# solo.net
KiCad netlist of a schematic drawn in EAGLE
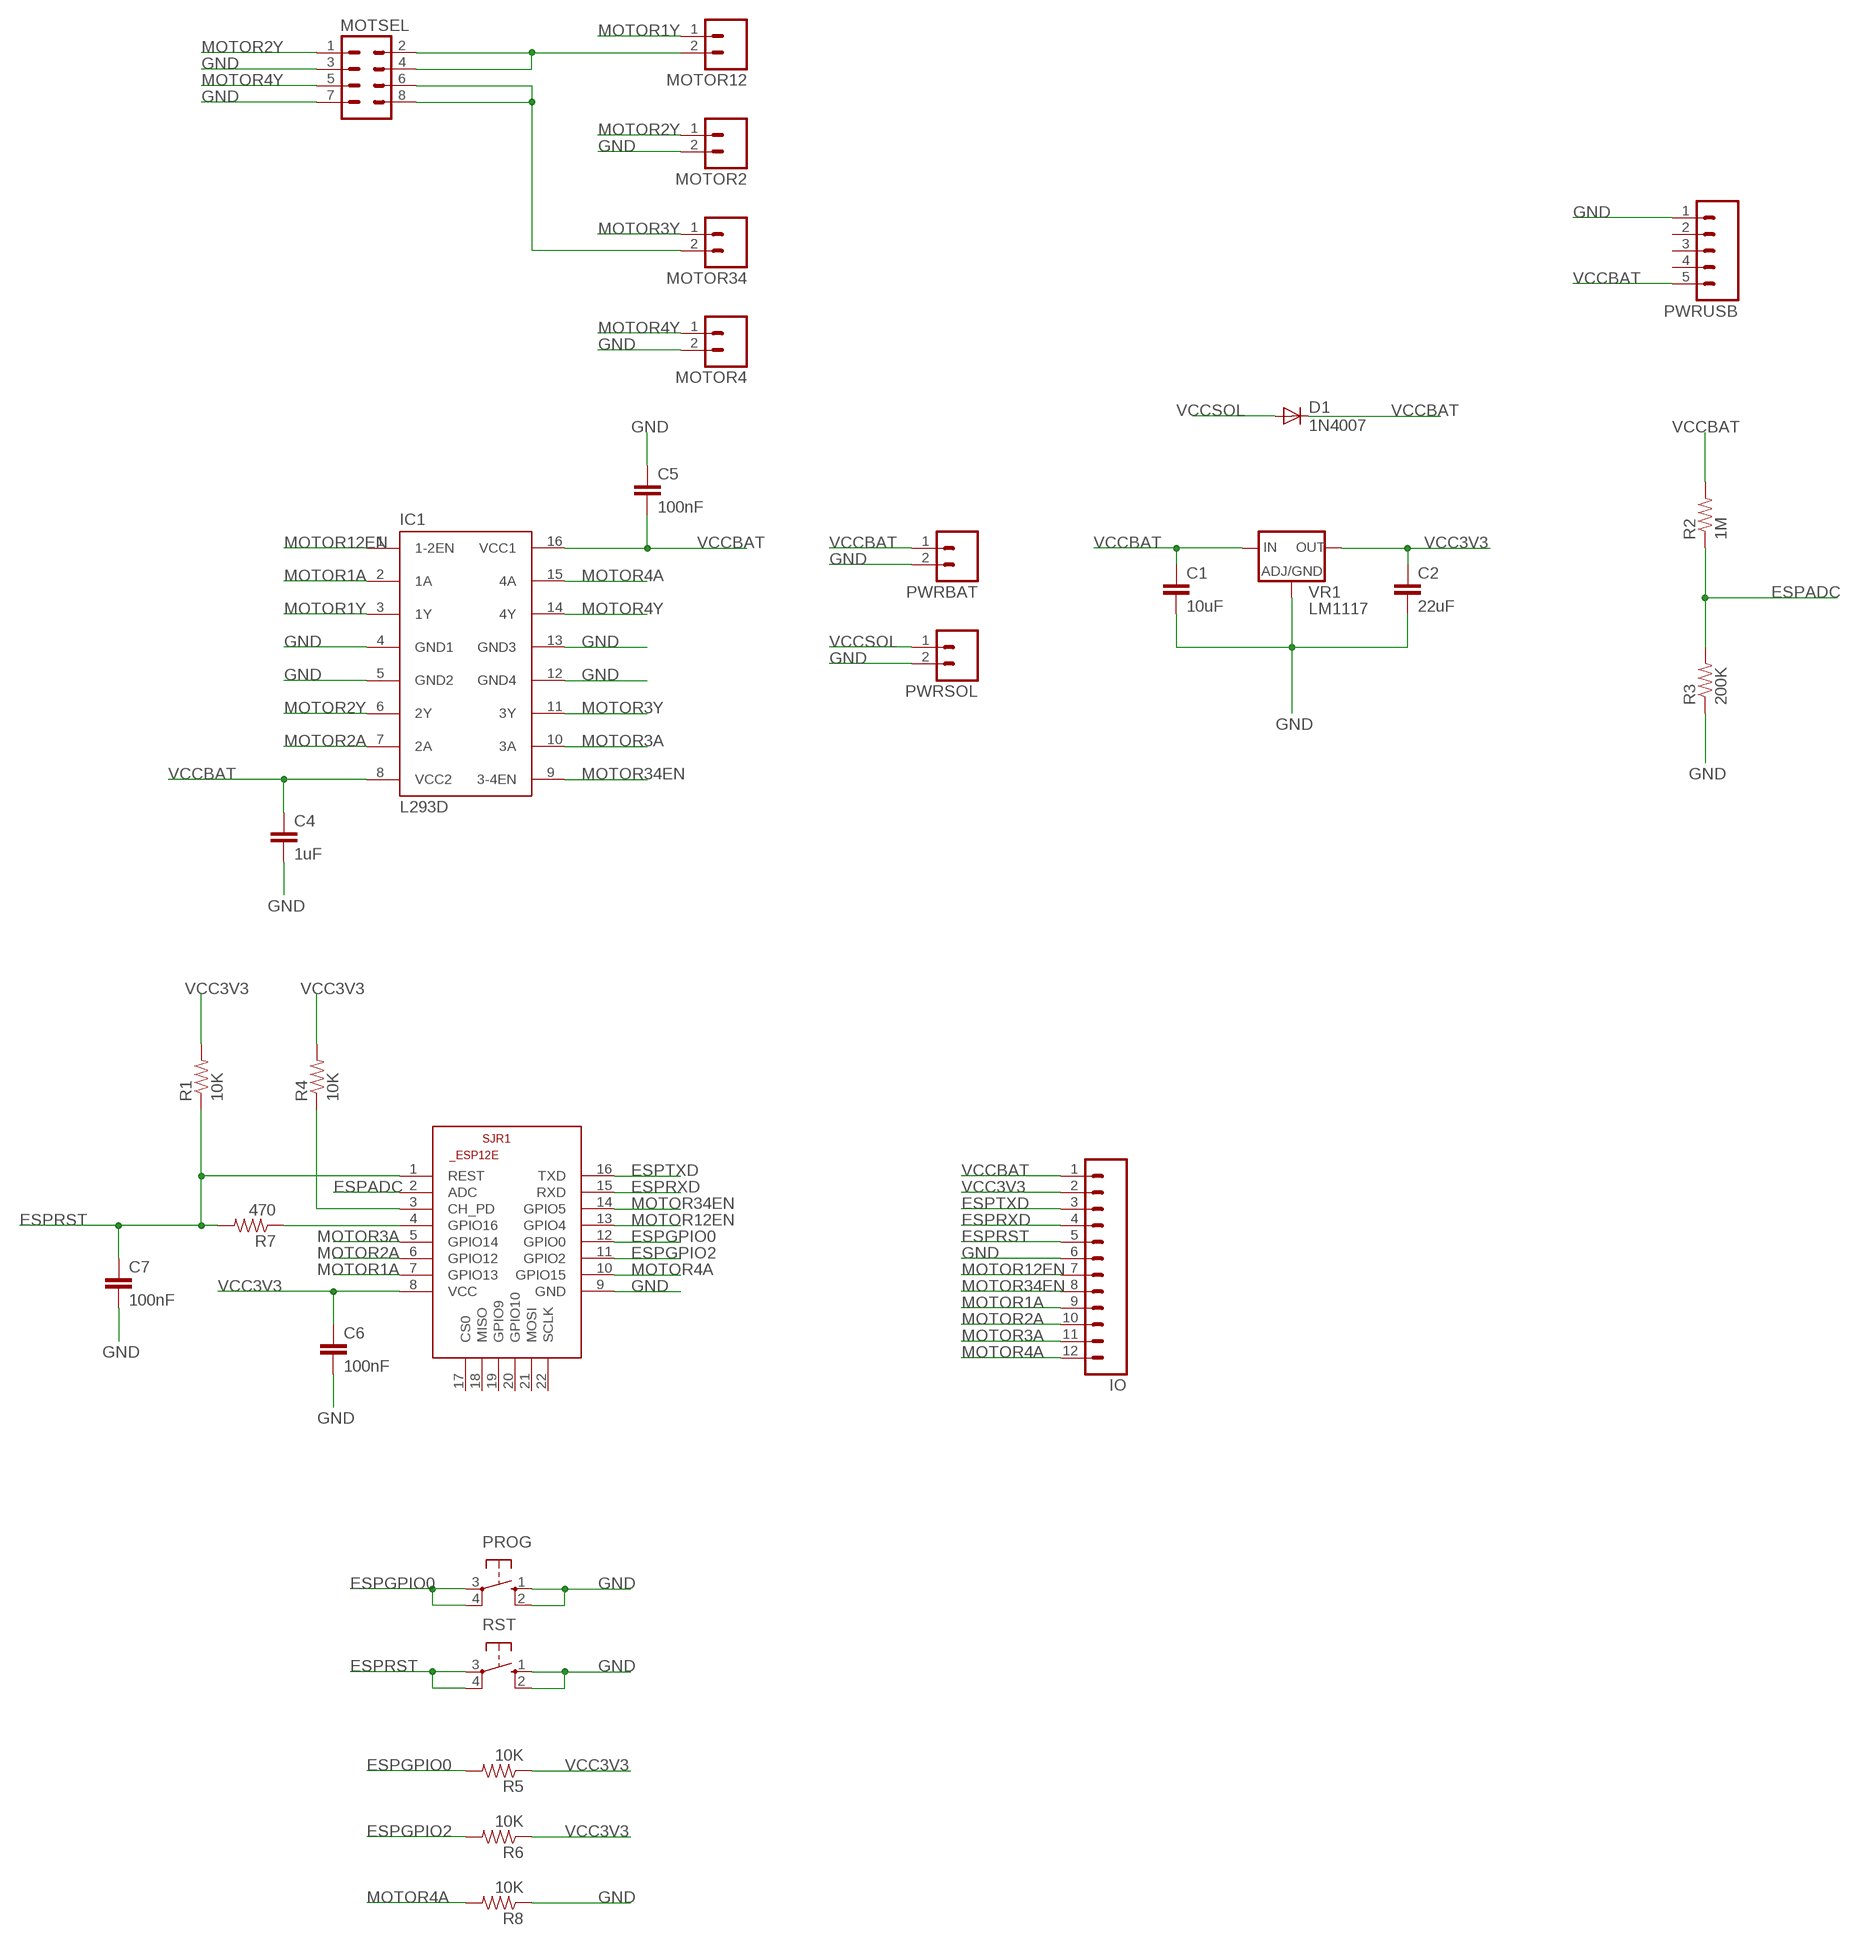
[diagram p0: schematic, sheet 1]

(export (version "E")
  (design (tool "Eeschema 10.0.6"))
  (components
    (comp (ref "C1")
      (value "10uF")
      (footprint "eagle-import:1206")
      (libsource (lib "eagle-import") (part "CAP1206"))
    )
    (comp (ref "C2")
      (value "22uF")
      (footprint "eagle-import:1206")
      (libsource (lib "eagle-import") (part "CAP1206"))
    )
    (comp (ref "C4")
      (value "1uF")
      (footprint "eagle-import:1206")
      (libsource (lib "eagle-import") (part "CAP1206"))
    )
    (comp (ref "C5")
      (value "100nF")
      (footprint "eagle-import:1206")
      (libsource (lib "eagle-import") (part "CAP1206"))
    )
    (comp (ref "C6")
      (value "100nF")
      (footprint "eagle-import:1206")
      (libsource (lib "eagle-import") (part "CAP1206"))
    )
    (comp (ref "C7")
      (value "100nF")
      (footprint "eagle-import:1206")
      (libsource (lib "eagle-import") (part "CAP1206"))
    )
    (comp (ref "D1")
      (value "1N4007")
      (footprint "eagle-import:DO41-10")
      (libsource (lib "eagle-import") (part "1N4004"))
    )
    (comp (ref "IC1")
      (value "L293D")
      (footprint "eagle-import:DIL16")
      (libsource (lib "eagle-import") (part "L293D"))
    )
    (comp (ref "IO")
      (value "M12PTH")
      (footprint "eagle-import:1X12")
      (libsource (lib "eagle-import") (part "M12PTH"))
    )
    (comp (ref "MOTOR2")
      (value "M023.5MM")
      (footprint "eagle-import:SCREWTERMINAL-3.5MM-2")
      (libsource (lib "eagle-import") (part "M023.5MM"))
    )
    (comp (ref "MOTOR4")
      (value "M023.5MM")
      (footprint "eagle-import:SCREWTERMINAL-3.5MM-2")
      (libsource (lib "eagle-import") (part "M023.5MM"))
    )
    (comp (ref "MOTOR12")
      (value "M023.5MM")
      (footprint "eagle-import:SCREWTERMINAL-3.5MM-2")
      (libsource (lib "eagle-import") (part "M023.5MM"))
    )
    (comp (ref "MOTOR34")
      (value "M023.5MM")
      (footprint "eagle-import:SCREWTERMINAL-3.5MM-2")
      (libsource (lib "eagle-import") (part "M023.5MM"))
    )
    (comp (ref "MOTSEL")
      (value "M04X2")
      (footprint "eagle-import:2X4")
      (libsource (lib "eagle-import") (part "M04X2"))
    )
    (comp (ref "PROG")
      (value "10-XX")
      (footprint "eagle-import:B3F-10XX")
      (fields (field (name "MPN") "B3F-1000"))
      (libsource (lib "eagle-import") (part "10-XX"))
    )
    (comp (ref "PWRBAT")
      (value "M023.5MM")
      (footprint "eagle-import:SCREWTERMINAL-3.5MM-2")
      (libsource (lib "eagle-import") (part "M023.5MM"))
    )
    (comp (ref "PWRSOL")
      (value "M023.5MM")
      (footprint "eagle-import:SCREWTERMINAL-3.5MM-2")
      (libsource (lib "eagle-import") (part "M023.5MM"))
    )
    (comp (ref "PWRUSB")
      (value "M05PTH")
      (footprint "eagle-import:1X05")
      (libsource (lib "eagle-import") (part "M05PTH"))
    )
    (comp (ref "R1")
      (value "10K")
      (footprint "eagle-import:1206")
      (libsource (lib "eagle-import") (part "RESISTOR1206"))
    )
    (comp (ref "R2")
      (value "1M")
      (footprint "eagle-import:1206")
      (libsource (lib "eagle-import") (part "RESISTOR1206"))
    )
    (comp (ref "R3")
      (value "200K")
      (footprint "eagle-import:1206")
      (libsource (lib "eagle-import") (part "RESISTOR1206"))
    )
    (comp (ref "R4")
      (value "10K")
      (footprint "eagle-import:1206")
      (libsource (lib "eagle-import") (part "RESISTOR1206"))
    )
    (comp (ref "R5")
      (value "10K")
      (footprint "eagle-import:1206")
      (libsource (lib "eagle-import") (part "RESISTOR1206"))
    )
    (comp (ref "R6")
      (value "10K")
      (footprint "eagle-import:1206")
      (libsource (lib "eagle-import") (part "RESISTOR1206"))
    )
    (comp (ref "R7")
      (value "470")
      (footprint "eagle-import:1206")
      (libsource (lib "eagle-import") (part "RESISTOR1206"))
    )
    (comp (ref "R8")
      (value "10K")
      (footprint "eagle-import:1206")
      (libsource (lib "eagle-import") (part "RESISTOR1206"))
    )
    (comp (ref "RST")
      (value "10-XX")
      (footprint "eagle-import:B3F-10XX")
      (fields (field (name "MPN") "B3F-1000"))
      (libsource (lib "eagle-import") (part "10-XX"))
    )
    (comp (ref "SJR1")
      (value "ESP8266-12EESP12E")
      (footprint "eagle-import:ESP8266-ESP12E")
      (libsource (lib "eagle-import") (part "ESP8266-12EESP12E"))
    )
    (comp (ref "VR1")
      (value "LM1117")
      (footprint "eagle-import:SOT223")
      (libsource (lib "eagle-import") (part "LM1117"))
    )
  )
  (nets
    (net (code "1") (name "/ESPADC") (class "Default")
      (node (ref "R2") (pin "1") (pinfunction "1_1") (pintype "passive"))
      (node (ref "R3") (pin "2") (pinfunction "2_2") (pintype "passive"))
      (node (ref "SJR1") (pin "2") (pinfunction "ADC_2") (pintype "bidirectional"))
    )
    (net (code "2") (name "/ESPGPIO0") (class "Default")
      (node (ref "PROG") (pin "3") (pinfunction "P_3") (pintype "passive"))
      (node (ref "PROG") (pin "4") (pinfunction "P1_4") (pintype "passive"))
      (node (ref "R5") (pin "2") (pinfunction "2_2") (pintype "passive"))
      (node (ref "SJR1") (pin "12") (pinfunction "GPIO0_12") (pintype "bidirectional"))
    )
    (net (code "3") (name "/ESPGPIO2") (class "Default")
      (node (ref "R6") (pin "2") (pinfunction "2_2") (pintype "passive"))
      (node (ref "SJR1") (pin "11") (pinfunction "GPIO2_11") (pintype "bidirectional"))
    )
    (net (code "4") (name "/ESPRST") (class "Default")
      (node (ref "C7") (pin "1") (pinfunction "1_1") (pintype "passive"))
      (node (ref "IO") (pin "5") (pinfunction "5_5") (pintype "passive"))
      (node (ref "R1") (pin "1") (pinfunction "1_1") (pintype "passive"))
      (node (ref "R7") (pin "2") (pinfunction "2_2") (pintype "passive"))
      (node (ref "RST") (pin "3") (pinfunction "P_3") (pintype "passive"))
      (node (ref "RST") (pin "4") (pinfunction "P1_4") (pintype "passive"))
      (node (ref "SJR1") (pin "1") (pinfunction "REST_1") (pintype "bidirectional"))
    )
    (net (code "5") (name "/ESPRXD") (class "Default")
      (node (ref "IO") (pin "4") (pinfunction "4_4") (pintype "passive"))
      (node (ref "SJR1") (pin "15") (pinfunction "RXD_15") (pintype "bidirectional"))
    )
    (net (code "6") (name "/ESPTXD") (class "Default")
      (node (ref "IO") (pin "3") (pinfunction "3_3") (pintype "passive"))
      (node (ref "SJR1") (pin "16") (pinfunction "TXD_16") (pintype "bidirectional"))
    )
    (net (code "7") (name "/GND") (class "Default")
      (node (ref "C1") (pin "2") (pinfunction "2_2") (pintype "passive"))
      (node (ref "C2") (pin "2") (pinfunction "2_2") (pintype "passive"))
      (node (ref "C4") (pin "2") (pinfunction "2_2") (pintype "passive"))
      (node (ref "C5") (pin "1") (pinfunction "1_1") (pintype "passive"))
      (node (ref "C6") (pin "2") (pinfunction "2_2") (pintype "passive"))
      (node (ref "C7") (pin "2") (pinfunction "2_2") (pintype "passive"))
      (node (ref "IC1") (pin "12") (pinfunction "GND4_12") (pintype "power_in"))
      (node (ref "IC1") (pin "13") (pinfunction "GND3_13") (pintype "power_in"))
      (node (ref "IC1") (pin "4") (pinfunction "GND1_4") (pintype "power_in"))
      (node (ref "IC1") (pin "5") (pinfunction "GND2_5") (pintype "power_in"))
      (node (ref "IO") (pin "6") (pinfunction "6_6") (pintype "passive"))
      (node (ref "MOTOR2") (pin "2") (pinfunction "2_2") (pintype "passive"))
      (node (ref "MOTOR4") (pin "2") (pinfunction "2_2") (pintype "passive"))
      (node (ref "MOTSEL") (pin "3") (pinfunction "3_3") (pintype "passive"))
      (node (ref "MOTSEL") (pin "7") (pinfunction "7_7") (pintype "passive"))
      (node (ref "PROG") (pin "1") (pinfunction "S_1") (pintype "passive"))
      (node (ref "PROG") (pin "2") (pinfunction "S1_2") (pintype "passive"))
      (node (ref "PWRBAT") (pin "2") (pinfunction "2_2") (pintype "passive"))
      (node (ref "PWRSOL") (pin "2") (pinfunction "2_2") (pintype "passive"))
      (node (ref "PWRUSB") (pin "1") (pinfunction "1_1") (pintype "passive"))
      (node (ref "R3") (pin "1") (pinfunction "1_1") (pintype "passive"))
      (node (ref "R8") (pin "1") (pinfunction "1_1") (pintype "passive"))
      (node (ref "RST") (pin "1") (pinfunction "S_1") (pintype "passive"))
      (node (ref "RST") (pin "2") (pinfunction "S1_2") (pintype "passive"))
      (node (ref "SJR1") (pin "9") (pinfunction "GND_9") (pintype "bidirectional"))
      (node (ref "VR1") (pin "1") (pinfunction "ADJ/GND_1") (pintype "power_in"))
    )
    (net (code "8") (name "/MOTOR1A") (class "Default")
      (node (ref "IC1") (pin "2") (pinfunction "1A_2") (pintype "input"))
      (node (ref "IO") (pin "9") (pinfunction "9_9") (pintype "passive"))
      (node (ref "SJR1") (pin "7") (pinfunction "GPIO13_7") (pintype "bidirectional"))
    )
    (net (code "9") (name "/MOTOR1Y") (class "Default")
      (node (ref "IC1") (pin "3") (pinfunction "1Y_3") (pintype "output"))
      (node (ref "MOTOR12") (pin "1") (pinfunction "1_1") (pintype "passive"))
    )
    (net (code "10") (name "/MOTOR2A") (class "Default")
      (node (ref "IC1") (pin "7") (pinfunction "2A_7") (pintype "input"))
      (node (ref "IO") (pin "10") (pinfunction "10_10") (pintype "passive"))
      (node (ref "SJR1") (pin "6") (pinfunction "GPIO12_6") (pintype "bidirectional"))
    )
    (net (code "11") (name "/MOTOR2Y") (class "Default")
      (node (ref "IC1") (pin "6") (pinfunction "2Y_6") (pintype "output"))
      (node (ref "MOTOR2") (pin "1") (pinfunction "1_1") (pintype "passive"))
      (node (ref "MOTSEL") (pin "1") (pinfunction "1_1") (pintype "passive"))
    )
    (net (code "12") (name "/MOTOR3A") (class "Default")
      (node (ref "IC1") (pin "10") (pinfunction "3A_10") (pintype "input"))
      (node (ref "IO") (pin "11") (pinfunction "11_11") (pintype "passive"))
      (node (ref "SJR1") (pin "5") (pinfunction "GPIO14_5") (pintype "bidirectional"))
    )
    (net (code "13") (name "/MOTOR3Y") (class "Default")
      (node (ref "IC1") (pin "11") (pinfunction "3Y_11") (pintype "output"))
      (node (ref "MOTOR34") (pin "1") (pinfunction "1_1") (pintype "passive"))
    )
    (net (code "14") (name "/MOTOR4A") (class "Default")
      (node (ref "IC1") (pin "15") (pinfunction "4A_15") (pintype "input"))
      (node (ref "IO") (pin "12") (pinfunction "12_12") (pintype "passive"))
      (node (ref "R8") (pin "2") (pinfunction "2_2") (pintype "passive"))
      (node (ref "SJR1") (pin "10") (pinfunction "GPIO15_10") (pintype "bidirectional"))
    )
    (net (code "15") (name "/MOTOR4Y") (class "Default")
      (node (ref "IC1") (pin "14") (pinfunction "4Y_14") (pintype "output"))
      (node (ref "MOTOR4") (pin "1") (pinfunction "1_1") (pintype "passive"))
      (node (ref "MOTSEL") (pin "5") (pinfunction "5_5") (pintype "passive"))
    )
    (net (code "16") (name "/MOTOR12EN") (class "Default")
      (node (ref "IC1") (pin "1") (pinfunction "1-2EN_1") (pintype "input"))
      (node (ref "IO") (pin "7") (pinfunction "7_7") (pintype "passive"))
      (node (ref "SJR1") (pin "13") (pinfunction "GPIO4_13") (pintype "bidirectional"))
    )
    (net (code "17") (name "/MOTOR34EN") (class "Default")
      (node (ref "IC1") (pin "9") (pinfunction "3-4EN_9") (pintype "input"))
      (node (ref "IO") (pin "8") (pinfunction "8_8") (pintype "passive"))
      (node (ref "SJR1") (pin "14") (pinfunction "GPIO5_14") (pintype "bidirectional"))
    )
    (net (code "18") (name "/VCC3V3") (class "Default")
      (node (ref "C2") (pin "1") (pinfunction "1_1") (pintype "passive"))
      (node (ref "C6") (pin "1") (pinfunction "1_1") (pintype "passive"))
      (node (ref "IO") (pin "2") (pinfunction "2_2") (pintype "passive"))
      (node (ref "R1") (pin "2") (pinfunction "2_2") (pintype "passive"))
      (node (ref "R4") (pin "2") (pinfunction "2_2") (pintype "passive"))
      (node (ref "R5") (pin "1") (pinfunction "1_1") (pintype "passive"))
      (node (ref "R6") (pin "1") (pinfunction "1_1") (pintype "passive"))
      (node (ref "SJR1") (pin "8") (pinfunction "VCC_8") (pintype "bidirectional"))
      (node (ref "VR1") (pin "2") (pinfunction "OUT_2") (pintype "power_in"))
    )
    (net (code "19") (name "/VCCBAT") (class "Default")
      (node (ref "C1") (pin "1") (pinfunction "1_1") (pintype "passive"))
      (node (ref "C4") (pin "1") (pinfunction "1_1") (pintype "passive"))
      (node (ref "C5") (pin "2") (pinfunction "2_2") (pintype "passive"))
      (node (ref "D1") (pin "C") (pinfunction "C_C") (pintype "passive"))
      (node (ref "IC1") (pin "16") (pinfunction "VCC1_16") (pintype "power_in"))
      (node (ref "IC1") (pin "8") (pinfunction "VCC2_8") (pintype "power_in"))
      (node (ref "IO") (pin "1") (pinfunction "1_1") (pintype "passive"))
      (node (ref "PWRBAT") (pin "1") (pinfunction "1_1") (pintype "passive"))
      (node (ref "PWRUSB") (pin "5") (pinfunction "5_5") (pintype "passive"))
      (node (ref "R2") (pin "2") (pinfunction "2_2") (pintype "passive"))
      (node (ref "VR1") (pin "3") (pinfunction "IN_3") (pintype "input"))
    )
    (net (code "20") (name "/VCCSOL") (class "Default")
      (node (ref "D1") (pin "A") (pinfunction "A_A") (pintype "passive"))
      (node (ref "PWRSOL") (pin "1") (pinfunction "1_1") (pintype "passive"))
    )
    (net (code "21") (name "Net-(MOTOR12-Pad2)") (class "Default")
      (node (ref "MOTOR12") (pin "2") (pinfunction "2_2") (pintype "passive"))
      (node (ref "MOTSEL") (pin "2") (pinfunction "2_2") (pintype "passive"))
      (node (ref "MOTSEL") (pin "4") (pinfunction "4_4") (pintype "passive"))
    )
    (net (code "22") (name "Net-(MOTOR34-Pad2)") (class "Default")
      (node (ref "MOTOR34") (pin "2") (pinfunction "2_2") (pintype "passive"))
      (node (ref "MOTSEL") (pin "6") (pinfunction "6_6") (pintype "passive"))
      (node (ref "MOTSEL") (pin "8") (pinfunction "8_8") (pintype "passive"))
    )
    (net (code "23") (name "Net-(SJR1-CH_PD)") (class "Default")
      (node (ref "R4") (pin "1") (pinfunction "1_1") (pintype "passive"))
      (node (ref "SJR1") (pin "3") (pinfunction "CH_PD_3") (pintype "bidirectional"))
    )
    (net (code "24") (name "Net-(SJR1-GPIO16)") (class "Default")
      (node (ref "R7") (pin "1") (pinfunction "1_1") (pintype "passive"))
      (node (ref "SJR1") (pin "4") (pinfunction "GPIO16_4") (pintype "bidirectional"))
    )
    (net (code "25") (name "unconnected-(PWRUSB-Pad2)") (class "Default")
      (node (ref "PWRUSB") (pin "2") (pinfunction "2_2") (pintype "passive"))
    )
    (net (code "26") (name "unconnected-(PWRUSB-Pad3)") (class "Default")
      (node (ref "PWRUSB") (pin "3") (pinfunction "3_3") (pintype "passive"))
    )
    (net (code "27") (name "unconnected-(PWRUSB-Pad4)") (class "Default")
      (node (ref "PWRUSB") (pin "4") (pinfunction "4_4") (pintype "passive"))
    )
    (net (code "28") (name "unconnected-(SJR1-CS0-Pad17)") (class "Default")
      (node (ref "SJR1") (pin "17") (pinfunction "CS0_17") (pintype "bidirectional"))
    )
    (net (code "29") (name "unconnected-(SJR1-GPIO9-Pad19)") (class "Default")
      (node (ref "SJR1") (pin "19") (pinfunction "GPIO9_19") (pintype "bidirectional"))
    )
    (net (code "30") (name "unconnected-(SJR1-GPIO10-Pad20)") (class "Default")
      (node (ref "SJR1") (pin "20") (pinfunction "GPIO10_20") (pintype "bidirectional"))
    )
    (net (code "31") (name "unconnected-(SJR1-MISO-Pad18)") (class "Default")
      (node (ref "SJR1") (pin "18") (pinfunction "MISO_18") (pintype "bidirectional"))
    )
    (net (code "32") (name "unconnected-(SJR1-MOSI-Pad21)") (class "Default")
      (node (ref "SJR1") (pin "21") (pinfunction "MOSI_21") (pintype "bidirectional"))
    )
    (net (code "33") (name "unconnected-(SJR1-SCLK-Pad22)") (class "Default")
      (node (ref "SJR1") (pin "22") (pinfunction "SCLK_22") (pintype "bidirectional"))
    )
  )
)
